# MA-Support.net
KiCad netlist of a schematic drawn in Altium Designer
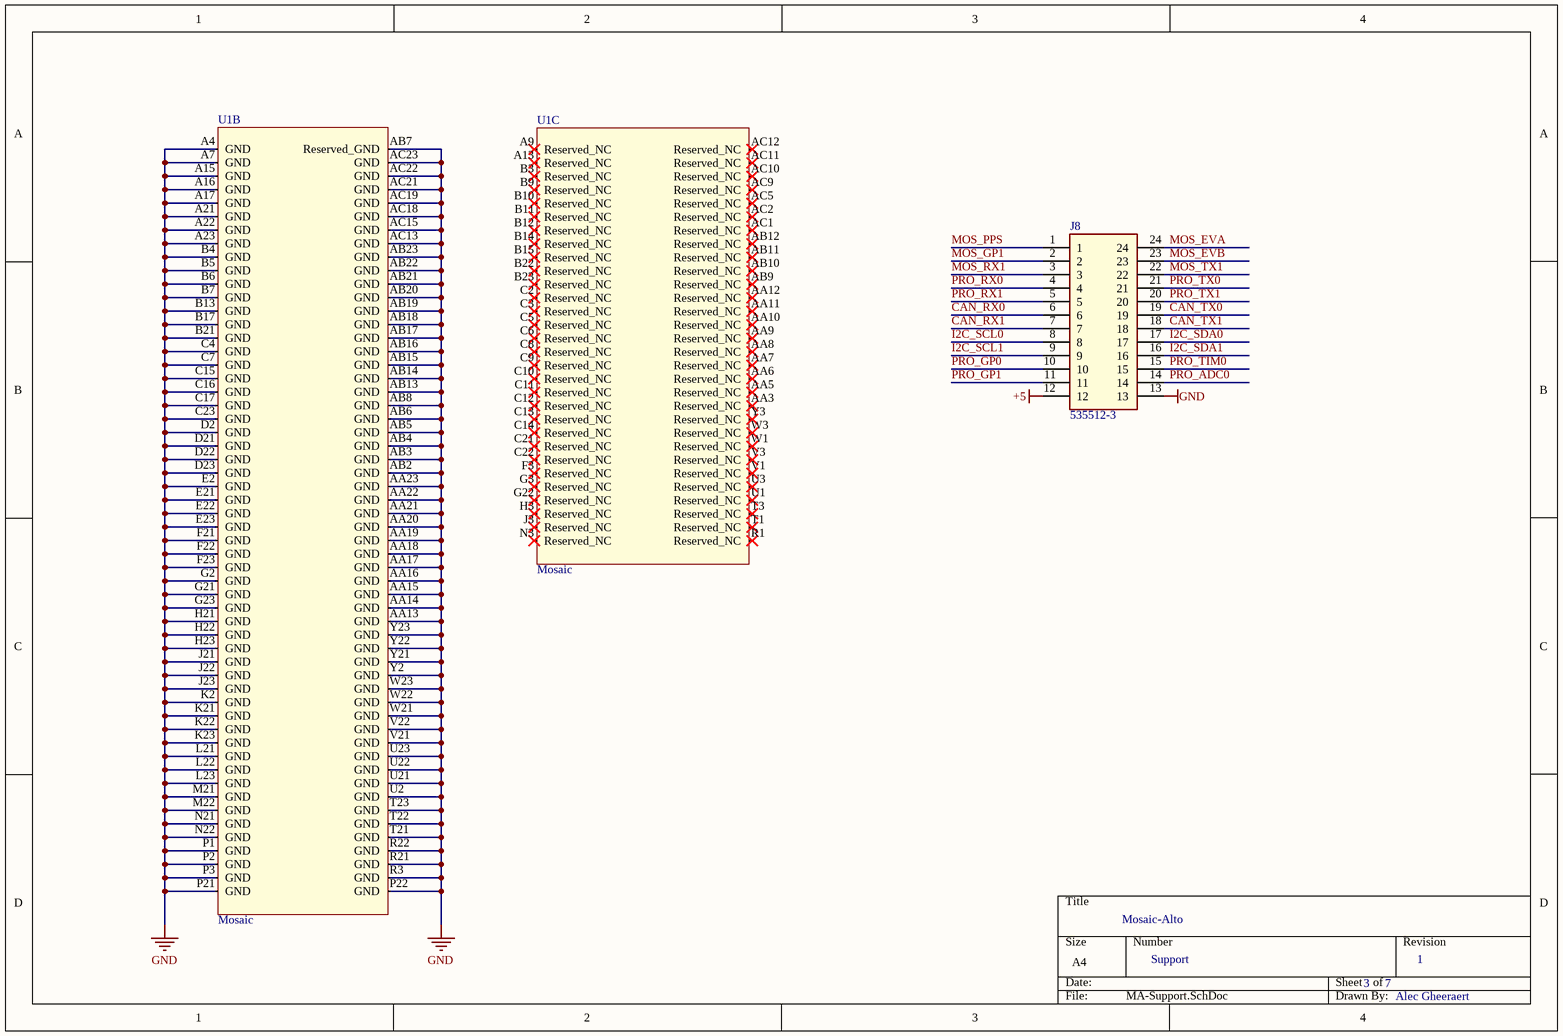
[diagram p0: MA-Support.SchDoc]

(export (version "E")
  (design (tool "Eeschema 10.0.6"))
  (components
    (comp (ref "J8")
      (value "535512-3")
      (footprint "5355123")
      (description "24 Pin Right Angle Female Header")
      (libsource (lib "Ghrt") (part "535512-3"))
    )
    (comp (ref "U1")
      (value "Mosaic")
      (footprint "Mosaic")
      (description "GNSS RTK Receiver")
      (fields (field (name "MANUFACTURER") "Septentrio"))
      (libsource (lib "Ghrt") (part "CMP-00013-3"))
    )
  )
  (nets
    (net (code "1") (name "+5") (class "Default")
      (node (ref "J8") (pin "12") (pinfunction "12_12") (pintype "passive"))
    )
    (net (code "2") (name "/CAN_RX0") (class "Default")
      (node (ref "J8") (pin "6") (pinfunction "6_6") (pintype "passive"))
    )
    (net (code "3") (name "/CAN_RX1") (class "Default")
      (node (ref "J8") (pin "7") (pinfunction "7_7") (pintype "passive"))
    )
    (net (code "4") (name "/CAN_TX0") (class "Default")
      (node (ref "J8") (pin "19") (pinfunction "19_19") (pintype "passive"))
    )
    (net (code "5") (name "/CAN_TX1") (class "Default")
      (node (ref "J8") (pin "18") (pinfunction "18_18") (pintype "passive"))
    )
    (net (code "6") (name "/I2C_SCL0") (class "Default")
      (node (ref "J8") (pin "8") (pinfunction "8_8") (pintype "passive"))
    )
    (net (code "7") (name "/I2C_SCL1") (class "Default")
      (node (ref "J8") (pin "9") (pinfunction "9_9") (pintype "passive"))
    )
    (net (code "8") (name "/I2C_SDA0") (class "Default")
      (node (ref "J8") (pin "17") (pinfunction "17_17") (pintype "passive"))
    )
    (net (code "9") (name "/I2C_SDA1") (class "Default")
      (node (ref "J8") (pin "16") (pinfunction "16_16") (pintype "passive"))
    )
    (net (code "10") (name "/MOS_EVA") (class "Default")
      (node (ref "J8") (pin "24") (pinfunction "24_24") (pintype "passive"))
    )
    (net (code "11") (name "/MOS_EVB") (class "Default")
      (node (ref "J8") (pin "23") (pinfunction "23_23") (pintype "passive"))
    )
    (net (code "12") (name "/MOS_GP1") (class "Default")
      (node (ref "J8") (pin "2") (pinfunction "2_2") (pintype "passive"))
    )
    (net (code "13") (name "/MOS_PPS") (class "Default")
      (node (ref "J8") (pin "1") (pinfunction "1_1") (pintype "passive"))
    )
    (net (code "14") (name "/MOS_RX1") (class "Default")
      (node (ref "J8") (pin "3") (pinfunction "3_3") (pintype "passive"))
    )
    (net (code "15") (name "/MOS_TX1") (class "Default")
      (node (ref "J8") (pin "22") (pinfunction "22_22") (pintype "passive"))
    )
    (net (code "16") (name "/PRO_ADC0") (class "Default")
      (node (ref "J8") (pin "14") (pinfunction "14_14") (pintype "passive"))
    )
    (net (code "17") (name "/PRO_GP0") (class "Default")
      (node (ref "J8") (pin "10") (pinfunction "10_10") (pintype "passive"))
    )
    (net (code "18") (name "/PRO_GP1") (class "Default")
      (node (ref "J8") (pin "11") (pinfunction "11_11") (pintype "passive"))
    )
    (net (code "19") (name "/PRO_RX0") (class "Default")
      (node (ref "J8") (pin "4") (pinfunction "4_4") (pintype "passive"))
    )
    (net (code "20") (name "/PRO_RX1") (class "Default")
      (node (ref "J8") (pin "5") (pinfunction "5_5") (pintype "passive"))
    )
    (net (code "21") (name "/PRO_TIM0") (class "Default")
      (node (ref "J8") (pin "15") (pinfunction "15_15") (pintype "passive"))
    )
    (net (code "22") (name "/PRO_TX0") (class "Default")
      (node (ref "J8") (pin "21") (pinfunction "21_21") (pintype "passive"))
    )
    (net (code "23") (name "/PRO_TX1") (class "Default")
      (node (ref "J8") (pin "20") (pinfunction "20_20") (pintype "passive"))
    )
    (net (code "24") (name "GND") (class "Default")
      (node (ref "J8") (pin "13") (pinfunction "13_13") (pintype "passive"))
      (node (ref "U1") (pin "A15") (pinfunction "GND_A15") (pintype "power_in"))
      (node (ref "U1") (pin "A16") (pinfunction "GND_A16") (pintype "power_in"))
      (node (ref "U1") (pin "A17") (pinfunction "GND_A17") (pintype "power_in"))
      (node (ref "U1") (pin "A21") (pinfunction "GND_A21") (pintype "power_in"))
      (node (ref "U1") (pin "A22") (pinfunction "GND_A22") (pintype "power_in"))
      (node (ref "U1") (pin "A23") (pinfunction "GND_A23") (pintype "power_in"))
      (node (ref "U1") (pin "A4") (pinfunction "GND_A4") (pintype "power_in"))
      (node (ref "U1") (pin "A7") (pinfunction "GND_A7") (pintype "power_in"))
      (node (ref "U1") (pin "AA13") (pinfunction "GND_AA13") (pintype "power_in"))
      (node (ref "U1") (pin "AA14") (pinfunction "GND_AA14") (pintype "power_in"))
      (node (ref "U1") (pin "AA15") (pinfunction "GND_AA15") (pintype "power_in"))
      (node (ref "U1") (pin "AA16") (pinfunction "GND_AA16") (pintype "power_in"))
      (node (ref "U1") (pin "AA17") (pinfunction "GND_AA17") (pintype "power_in"))
      (node (ref "U1") (pin "AA18") (pinfunction "GND_AA18") (pintype "power_in"))
      (node (ref "U1") (pin "AA19") (pinfunction "GND_AA19") (pintype "power_in"))
      (node (ref "U1") (pin "AA20") (pinfunction "GND_AA20") (pintype "power_in"))
      (node (ref "U1") (pin "AA21") (pinfunction "GND_AA21") (pintype "power_in"))
      (node (ref "U1") (pin "AA22") (pinfunction "GND_AA22") (pintype "power_in"))
      (node (ref "U1") (pin "AA23") (pinfunction "GND_AA23") (pintype "power_in"))
      (node (ref "U1") (pin "AB13") (pinfunction "GND_AB13") (pintype "power_in"))
      (node (ref "U1") (pin "AB14") (pinfunction "GND_AB14") (pintype "power_in"))
      (node (ref "U1") (pin "AB15") (pinfunction "GND_AB15") (pintype "power_in"))
      (node (ref "U1") (pin "AB16") (pinfunction "GND_AB16") (pintype "power_in"))
      (node (ref "U1") (pin "AB17") (pinfunction "GND_AB17") (pintype "power_in"))
      (node (ref "U1") (pin "AB18") (pinfunction "GND_AB18") (pintype "power_in"))
      (node (ref "U1") (pin "AB19") (pinfunction "GND_AB19") (pintype "power_in"))
      (node (ref "U1") (pin "AB2") (pinfunction "GND_AB2") (pintype "power_in"))
      (node (ref "U1") (pin "AB20") (pinfunction "GND_AB20") (pintype "power_in"))
      (node (ref "U1") (pin "AB21") (pinfunction "GND_AB21") (pintype "power_in"))
      (node (ref "U1") (pin "AB22") (pinfunction "GND_AB22") (pintype "power_in"))
      (node (ref "U1") (pin "AB23") (pinfunction "GND_AB23") (pintype "power_in"))
      (node (ref "U1") (pin "AB3") (pinfunction "GND_AB3") (pintype "power_in"))
      (node (ref "U1") (pin "AB4") (pinfunction "GND_AB4") (pintype "power_in"))
      (node (ref "U1") (pin "AB5") (pinfunction "GND_AB5") (pintype "power_in"))
      (node (ref "U1") (pin "AB6") (pinfunction "GND_AB6") (pintype "power_in"))
      (node (ref "U1") (pin "AB7") (pinfunction "Reserved_GND_AB7") (pintype "power_in"))
      (node (ref "U1") (pin "AB8") (pinfunction "GND_AB8") (pintype "power_in"))
      (node (ref "U1") (pin "AC13") (pinfunction "GND_AC13") (pintype "power_in"))
      (node (ref "U1") (pin "AC15") (pinfunction "GND_AC15") (pintype "power_in"))
      (node (ref "U1") (pin "AC18") (pinfunction "GND_AC18") (pintype "power_in"))
      (node (ref "U1") (pin "AC19") (pinfunction "GND_AC19") (pintype "power_in"))
      (node (ref "U1") (pin "AC21") (pinfunction "GND_AC21") (pintype "power_in"))
      (node (ref "U1") (pin "AC22") (pinfunction "GND_AC22") (pintype "power_in"))
      (node (ref "U1") (pin "AC23") (pinfunction "GND_AC23") (pintype "power_in"))
      (node (ref "U1") (pin "B13") (pinfunction "GND_B13") (pintype "power_in"))
      (node (ref "U1") (pin "B17") (pinfunction "GND_B17") (pintype "power_in"))
      (node (ref "U1") (pin "B21") (pinfunction "GND_B21") (pintype "power_in"))
      (node (ref "U1") (pin "B4") (pinfunction "GND_B4") (pintype "power_in"))
      (node (ref "U1") (pin "B5") (pinfunction "GND_B5") (pintype "power_in"))
      (node (ref "U1") (pin "B6") (pinfunction "GND_B6") (pintype "power_in"))
      (node (ref "U1") (pin "B7") (pinfunction "GND_B7") (pintype "power_in"))
      (node (ref "U1") (pin "C15") (pinfunction "GND_C15") (pintype "power_in"))
      (node (ref "U1") (pin "C16") (pinfunction "GND_C16") (pintype "power_in"))
      (node (ref "U1") (pin "C17") (pinfunction "GND_C17") (pintype "power_in"))
      (node (ref "U1") (pin "C23") (pinfunction "GND_C23") (pintype "power_in"))
      (node (ref "U1") (pin "C4") (pinfunction "GND_C4") (pintype "power_in"))
      (node (ref "U1") (pin "C7") (pinfunction "GND_C7") (pintype "power_in"))
      (node (ref "U1") (pin "D2") (pinfunction "GND_D2") (pintype "power_in"))
      (node (ref "U1") (pin "D21") (pinfunction "GND_D21") (pintype "power_in"))
      (node (ref "U1") (pin "D22") (pinfunction "GND_D22") (pintype "power_in"))
      (node (ref "U1") (pin "D23") (pinfunction "GND_D23") (pintype "power_in"))
      (node (ref "U1") (pin "E2") (pinfunction "GND_E2") (pintype "power_in"))
      (node (ref "U1") (pin "E21") (pinfunction "GND_E21") (pintype "power_in"))
      (node (ref "U1") (pin "E22") (pinfunction "GND_E22") (pintype "power_in"))
      (node (ref "U1") (pin "E23") (pinfunction "GND_E23") (pintype "power_in"))
      (node (ref "U1") (pin "F21") (pinfunction "GND_F21") (pintype "power_in"))
      (node (ref "U1") (pin "F22") (pinfunction "GND_F22") (pintype "power_in"))
      (node (ref "U1") (pin "F23") (pinfunction "GND_F23") (pintype "power_in"))
      (node (ref "U1") (pin "G2") (pinfunction "GND_G2") (pintype "power_in"))
      (node (ref "U1") (pin "G21") (pinfunction "GND_G21") (pintype "power_in"))
      (node (ref "U1") (pin "G23") (pinfunction "GND_G23") (pintype "power_in"))
      (node (ref "U1") (pin "H21") (pinfunction "GND_H21") (pintype "power_in"))
      (node (ref "U1") (pin "H22") (pinfunction "GND_H22") (pintype "power_in"))
      (node (ref "U1") (pin "H23") (pinfunction "GND_H23") (pintype "power_in"))
      (node (ref "U1") (pin "J21") (pinfunction "GND_J21") (pintype "power_in"))
      (node (ref "U1") (pin "J22") (pinfunction "GND_J22") (pintype "power_in"))
      (node (ref "U1") (pin "J23") (pinfunction "GND_J23") (pintype "power_in"))
      (node (ref "U1") (pin "K2") (pinfunction "GND_K2") (pintype "power_in"))
      (node (ref "U1") (pin "K21") (pinfunction "GND_K21") (pintype "power_in"))
      (node (ref "U1") (pin "K22") (pinfunction "GND_K22") (pintype "power_in"))
      (node (ref "U1") (pin "K23") (pinfunction "GND_K23") (pintype "power_in"))
      (node (ref "U1") (pin "L21") (pinfunction "GND_L21") (pintype "power_in"))
      (node (ref "U1") (pin "L22") (pinfunction "GND_L22") (pintype "power_in"))
      (node (ref "U1") (pin "L23") (pinfunction "GND_L23") (pintype "power_in"))
      (node (ref "U1") (pin "M21") (pinfunction "GND_M21") (pintype "power_in"))
      (node (ref "U1") (pin "M22") (pinfunction "GND_M22") (pintype "power_in"))
      (node (ref "U1") (pin "N21") (pinfunction "GND_N21") (pintype "power_in"))
      (node (ref "U1") (pin "N22") (pinfunction "GND_N22") (pintype "power_in"))
      (node (ref "U1") (pin "P1") (pinfunction "GND_P1") (pintype "power_in"))
      (node (ref "U1") (pin "P2") (pinfunction "GND_P2") (pintype "power_in"))
      (node (ref "U1") (pin "P21") (pinfunction "GND_P21") (pintype "power_in"))
      (node (ref "U1") (pin "P22") (pinfunction "GND_P22") (pintype "power_in"))
      (node (ref "U1") (pin "P3") (pinfunction "GND_P3") (pintype "power_in"))
      (node (ref "U1") (pin "R21") (pinfunction "GND_R21") (pintype "power_in"))
      (node (ref "U1") (pin "R22") (pinfunction "GND_R22") (pintype "power_in"))
      (node (ref "U1") (pin "R3") (pinfunction "GND_R3") (pintype "power_in"))
      (node (ref "U1") (pin "T21") (pinfunction "GND_T21") (pintype "power_in"))
      (node (ref "U1") (pin "T22") (pinfunction "GND_T22") (pintype "power_in"))
      (node (ref "U1") (pin "T23") (pinfunction "GND_T23") (pintype "power_in"))
      (node (ref "U1") (pin "U2") (pinfunction "GND_U2") (pintype "power_in"))
      (node (ref "U1") (pin "U21") (pinfunction "GND_U21") (pintype "power_in"))
      (node (ref "U1") (pin "U22") (pinfunction "GND_U22") (pintype "power_in"))
      (node (ref "U1") (pin "U23") (pinfunction "GND_U23") (pintype "power_in"))
      (node (ref "U1") (pin "V21") (pinfunction "GND_V21") (pintype "power_in"))
      (node (ref "U1") (pin "V22") (pinfunction "GND_V22") (pintype "power_in"))
      (node (ref "U1") (pin "W21") (pinfunction "GND_W21") (pintype "power_in"))
      (node (ref "U1") (pin "W22") (pinfunction "GND_W22") (pintype "power_in"))
      (node (ref "U1") (pin "W23") (pinfunction "GND_W23") (pintype "power_in"))
      (node (ref "U1") (pin "Y2") (pinfunction "GND_Y2") (pintype "power_in"))
      (node (ref "U1") (pin "Y21") (pinfunction "GND_Y21") (pintype "power_in"))
      (node (ref "U1") (pin "Y22") (pinfunction "GND_Y22") (pintype "power_in"))
      (node (ref "U1") (pin "Y23") (pinfunction "GND_Y23") (pintype "power_in"))
    )
    (net (code "25") (name "unconnected-(U1C-Reserved_NC-PadA9)") (class "Default")
      (node (ref "U1") (pin "A9") (pinfunction "Reserved_NC_A9") (pintype "passive+no_connect"))
    )
    (net (code "26") (name "unconnected-(U1C-Reserved_NC-PadA13)") (class "Default")
      (node (ref "U1") (pin "A13") (pinfunction "Reserved_NC_A13") (pintype "passive+no_connect"))
    )
    (net (code "27") (name "unconnected-(U1C-Reserved_NC-PadAA3)") (class "Default")
      (node (ref "U1") (pin "AA3") (pinfunction "Reserved_NC_AA3") (pintype "passive+no_connect"))
    )
    (net (code "28") (name "unconnected-(U1C-Reserved_NC-PadAA5)") (class "Default")
      (node (ref "U1") (pin "AA5") (pinfunction "Reserved_NC_AA5") (pintype "passive+no_connect"))
    )
    (net (code "29") (name "unconnected-(U1C-Reserved_NC-PadAA6)") (class "Default")
      (node (ref "U1") (pin "AA6") (pinfunction "Reserved_NC_AA6") (pintype "passive+no_connect"))
    )
    (net (code "30") (name "unconnected-(U1C-Reserved_NC-PadAA7)") (class "Default")
      (node (ref "U1") (pin "AA7") (pinfunction "Reserved_NC_AA7") (pintype "passive+no_connect"))
    )
    (net (code "31") (name "unconnected-(U1C-Reserved_NC-PadAA8)") (class "Default")
      (node (ref "U1") (pin "AA8") (pinfunction "Reserved_NC_AA8") (pintype "passive+no_connect"))
    )
    (net (code "32") (name "unconnected-(U1C-Reserved_NC-PadAA9)") (class "Default")
      (node (ref "U1") (pin "AA9") (pinfunction "Reserved_NC_AA9") (pintype "passive+no_connect"))
    )
    (net (code "33") (name "unconnected-(U1C-Reserved_NC-PadAA10)") (class "Default")
      (node (ref "U1") (pin "AA10") (pinfunction "Reserved_NC_AA10") (pintype "passive+no_connect"))
    )
    (net (code "34") (name "unconnected-(U1C-Reserved_NC-PadAA11)") (class "Default")
      (node (ref "U1") (pin "AA11") (pinfunction "Reserved_NC_AA11") (pintype "passive+no_connect"))
    )
    (net (code "35") (name "unconnected-(U1C-Reserved_NC-PadAA12)") (class "Default")
      (node (ref "U1") (pin "AA12") (pinfunction "Reserved_NC_AA12") (pintype "passive+no_connect"))
    )
    (net (code "36") (name "unconnected-(U1C-Reserved_NC-PadAB9)") (class "Default")
      (node (ref "U1") (pin "AB9") (pinfunction "Reserved_NC_AB9") (pintype "passive+no_connect"))
    )
    (net (code "37") (name "unconnected-(U1C-Reserved_NC-PadAB10)") (class "Default")
      (node (ref "U1") (pin "AB10") (pinfunction "Reserved_NC_AB10") (pintype "passive+no_connect"))
    )
    (net (code "38") (name "unconnected-(U1C-Reserved_NC-PadAB11)") (class "Default")
      (node (ref "U1") (pin "AB11") (pinfunction "Reserved_NC_AB11") (pintype "passive+no_connect"))
    )
    (net (code "39") (name "unconnected-(U1C-Reserved_NC-PadAB12)") (class "Default")
      (node (ref "U1") (pin "AB12") (pinfunction "Reserved_NC_AB12") (pintype "passive+no_connect"))
    )
    (net (code "40") (name "unconnected-(U1C-Reserved_NC-PadAC1)") (class "Default")
      (node (ref "U1") (pin "AC1") (pinfunction "Reserved_NC_AC1") (pintype "passive+no_connect"))
    )
    (net (code "41") (name "unconnected-(U1C-Reserved_NC-PadAC2)") (class "Default")
      (node (ref "U1") (pin "AC2") (pinfunction "Reserved_NC_AC2") (pintype "passive+no_connect"))
    )
    (net (code "42") (name "unconnected-(U1C-Reserved_NC-PadAC5)") (class "Default")
      (node (ref "U1") (pin "AC5") (pinfunction "Reserved_NC_AC5") (pintype "passive+no_connect"))
    )
    (net (code "43") (name "unconnected-(U1C-Reserved_NC-PadAC9)") (class "Default")
      (node (ref "U1") (pin "AC9") (pinfunction "Reserved_NC_AC9") (pintype "passive+no_connect"))
    )
    (net (code "44") (name "unconnected-(U1C-Reserved_NC-PadAC10)") (class "Default")
      (node (ref "U1") (pin "AC10") (pinfunction "Reserved_NC_AC10") (pintype "passive+no_connect"))
    )
    (net (code "45") (name "unconnected-(U1C-Reserved_NC-PadAC11)") (class "Default")
      (node (ref "U1") (pin "AC11") (pinfunction "Reserved_NC_AC11") (pintype "passive+no_connect"))
    )
    (net (code "46") (name "unconnected-(U1C-Reserved_NC-PadAC12)") (class "Default")
      (node (ref "U1") (pin "AC12") (pinfunction "Reserved_NC_AC12") (pintype "passive+no_connect"))
    )
    (net (code "47") (name "unconnected-(U1C-Reserved_NC-PadB3)") (class "Default")
      (node (ref "U1") (pin "B3") (pinfunction "Reserved_NC_B3") (pintype "passive+no_connect"))
    )
    (net (code "48") (name "unconnected-(U1C-Reserved_NC-PadB9)") (class "Default")
      (node (ref "U1") (pin "B9") (pinfunction "Reserved_NC_B9") (pintype "passive+no_connect"))
    )
    (net (code "49") (name "unconnected-(U1C-Reserved_NC-PadB10)") (class "Default")
      (node (ref "U1") (pin "B10") (pinfunction "Reserved_NC_B10") (pintype "passive+no_connect"))
    )
    (net (code "50") (name "unconnected-(U1C-Reserved_NC-PadB11)") (class "Default")
      (node (ref "U1") (pin "B11") (pinfunction "Reserved_NC_B11") (pintype "passive+no_connect"))
    )
    (net (code "51") (name "unconnected-(U1C-Reserved_NC-PadB12)") (class "Default")
      (node (ref "U1") (pin "B12") (pinfunction "Reserved_NC_B12") (pintype "passive+no_connect"))
    )
    (net (code "52") (name "unconnected-(U1C-Reserved_NC-PadB14)") (class "Default")
      (node (ref "U1") (pin "B14") (pinfunction "Reserved_NC_B14") (pintype "passive+no_connect"))
    )
    (net (code "53") (name "unconnected-(U1C-Reserved_NC-PadB15)") (class "Default")
      (node (ref "U1") (pin "B15") (pinfunction "Reserved_NC_B15") (pintype "passive+no_connect"))
    )
    (net (code "54") (name "unconnected-(U1C-Reserved_NC-PadB22)") (class "Default")
      (node (ref "U1") (pin "B22") (pinfunction "Reserved_NC_B22") (pintype "passive+no_connect"))
    )
    (net (code "55") (name "unconnected-(U1C-Reserved_NC-PadB23)") (class "Default")
      (node (ref "U1") (pin "B23") (pinfunction "Reserved_NC_B23") (pintype "passive+no_connect"))
    )
    (net (code "56") (name "unconnected-(U1C-Reserved_NC-PadC2)") (class "Default")
      (node (ref "U1") (pin "C2") (pinfunction "Reserved_NC_C2") (pintype "passive+no_connect"))
    )
    (net (code "57") (name "unconnected-(U1C-Reserved_NC-PadC3)") (class "Default")
      (node (ref "U1") (pin "C3") (pinfunction "Reserved_NC_C3") (pintype "passive+no_connect"))
    )
    (net (code "58") (name "unconnected-(U1C-Reserved_NC-PadC5)") (class "Default")
      (node (ref "U1") (pin "C5") (pinfunction "Reserved_NC_C5") (pintype "passive+no_connect"))
    )
    (net (code "59") (name "unconnected-(U1C-Reserved_NC-PadC6)") (class "Default")
      (node (ref "U1") (pin "C6") (pinfunction "Reserved_NC_C6") (pintype "passive+no_connect"))
    )
    (net (code "60") (name "unconnected-(U1C-Reserved_NC-PadC8)") (class "Default")
      (node (ref "U1") (pin "C8") (pinfunction "Reserved_NC_C8") (pintype "passive+no_connect"))
    )
    (net (code "61") (name "unconnected-(U1C-Reserved_NC-PadC9)") (class "Default")
      (node (ref "U1") (pin "C9") (pinfunction "Reserved_NC_C9") (pintype "passive+no_connect"))
    )
    (net (code "62") (name "unconnected-(U1C-Reserved_NC-PadC10)") (class "Default")
      (node (ref "U1") (pin "C10") (pinfunction "Reserved_NC_C10") (pintype "passive+no_connect"))
    )
    (net (code "63") (name "unconnected-(U1C-Reserved_NC-PadC11)") (class "Default")
      (node (ref "U1") (pin "C11") (pinfunction "Reserved_NC_C11") (pintype "passive+no_connect"))
    )
    (net (code "64") (name "unconnected-(U1C-Reserved_NC-PadC12)") (class "Default")
      (node (ref "U1") (pin "C12") (pinfunction "Reserved_NC_C12") (pintype "passive+no_connect"))
    )
    (net (code "65") (name "unconnected-(U1C-Reserved_NC-PadC13)") (class "Default")
      (node (ref "U1") (pin "C13") (pinfunction "Reserved_NC_C13") (pintype "passive+no_connect"))
    )
    (net (code "66") (name "unconnected-(U1C-Reserved_NC-PadC14)") (class "Default")
      (node (ref "U1") (pin "C14") (pinfunction "Reserved_NC_C14") (pintype "passive+no_connect"))
    )
    (net (code "67") (name "unconnected-(U1C-Reserved_NC-PadC21)") (class "Default")
      (node (ref "U1") (pin "C21") (pinfunction "Reserved_NC_C21") (pintype "passive+no_connect"))
    )
    (net (code "68") (name "unconnected-(U1C-Reserved_NC-PadC22)") (class "Default")
      (node (ref "U1") (pin "C22") (pinfunction "Reserved_NC_C22") (pintype "passive+no_connect"))
    )
    (net (code "69") (name "unconnected-(U1C-Reserved_NC-PadF3)") (class "Default")
      (node (ref "U1") (pin "F3") (pinfunction "Reserved_NC_F3") (pintype "passive+no_connect"))
    )
    (net (code "70") (name "unconnected-(U1C-Reserved_NC-PadG3)") (class "Default")
      (node (ref "U1") (pin "G3") (pinfunction "Reserved_NC_G3") (pintype "passive+no_connect"))
    )
    (net (code "71") (name "unconnected-(U1C-Reserved_NC-PadG22)") (class "Default")
      (node (ref "U1") (pin "G22") (pinfunction "Reserved_NC_G22") (pintype "passive+no_connect"))
    )
    (net (code "72") (name "unconnected-(U1C-Reserved_NC-PadH3)") (class "Default")
      (node (ref "U1") (pin "H3") (pinfunction "Reserved_NC_H3") (pintype "passive+no_connect"))
    )
    (net (code "73") (name "unconnected-(U1C-Reserved_NC-PadJ3)") (class "Default")
      (node (ref "U1") (pin "J3") (pinfunction "Reserved_NC_J3") (pintype "passive+no_connect"))
    )
    (net (code "74") (name "unconnected-(U1C-Reserved_NC-PadN3)") (class "Default")
      (node (ref "U1") (pin "N3") (pinfunction "Reserved_NC_N3") (pintype "passive+no_connect"))
    )
    (net (code "75") (name "unconnected-(U1C-Reserved_NC-PadR1)") (class "Default")
      (node (ref "U1") (pin "R1") (pinfunction "Reserved_NC_R1") (pintype "passive+no_connect"))
    )
    (net (code "76") (name "unconnected-(U1C-Reserved_NC-PadT1)") (class "Default")
      (node (ref "U1") (pin "T1") (pinfunction "Reserved_NC_T1") (pintype "passive+no_connect"))
    )
    (net (code "77") (name "unconnected-(U1C-Reserved_NC-PadT3)") (class "Default")
      (node (ref "U1") (pin "T3") (pinfunction "Reserved_NC_T3") (pintype "passive+no_connect"))
    )
    (net (code "78") (name "unconnected-(U1C-Reserved_NC-PadU1)") (class "Default")
      (node (ref "U1") (pin "U1") (pinfunction "Reserved_NC_U1") (pintype "passive+no_connect"))
    )
    (net (code "79") (name "unconnected-(U1C-Reserved_NC-PadU3)") (class "Default")
      (node (ref "U1") (pin "U3") (pinfunction "Reserved_NC_U3") (pintype "passive+no_connect"))
    )
    (net (code "80") (name "unconnected-(U1C-Reserved_NC-PadV1)") (class "Default")
      (node (ref "U1") (pin "V1") (pinfunction "Reserved_NC_V1") (pintype "passive+no_connect"))
    )
    (net (code "81") (name "unconnected-(U1C-Reserved_NC-PadV3)") (class "Default")
      (node (ref "U1") (pin "V3") (pinfunction "Reserved_NC_V3") (pintype "passive+no_connect"))
    )
    (net (code "82") (name "unconnected-(U1C-Reserved_NC-PadW1)") (class "Default")
      (node (ref "U1") (pin "W1") (pinfunction "Reserved_NC_W1") (pintype "passive+no_connect"))
    )
    (net (code "83") (name "unconnected-(U1C-Reserved_NC-PadW3)") (class "Default")
      (node (ref "U1") (pin "W3") (pinfunction "Reserved_NC_W3") (pintype "passive+no_connect"))
    )
    (net (code "84") (name "unconnected-(U1C-Reserved_NC-PadY3)") (class "Default")
      (node (ref "U1") (pin "Y3") (pinfunction "Reserved_NC_Y3") (pintype "passive+no_connect"))
    )
  )
)
